# thermostat1.net
KiCad netlist of a schematic drawn in EAGLE
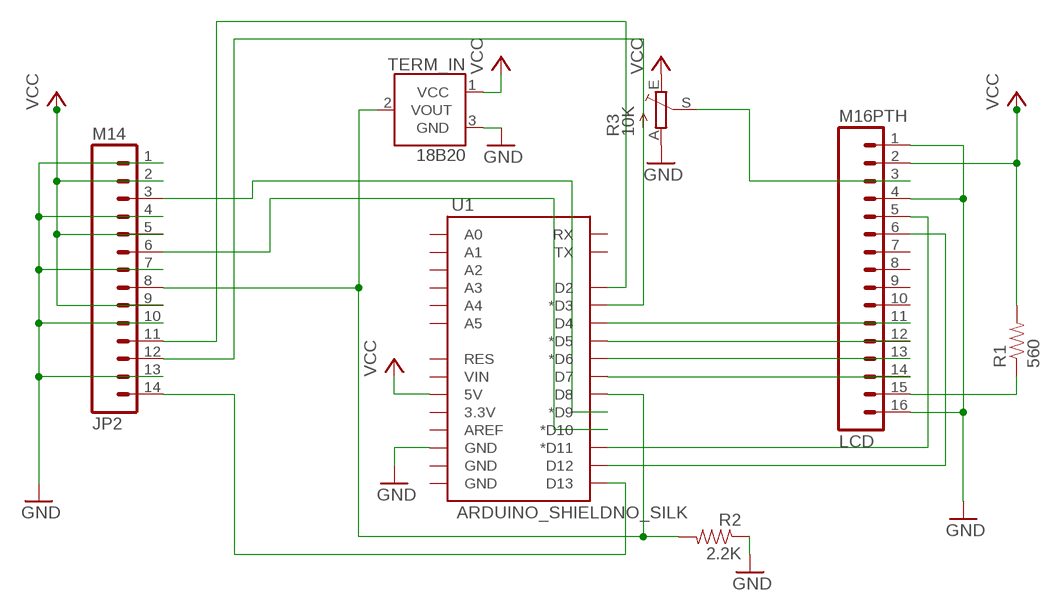
[diagram p0: schematic, sheet 1]

(export (version "E")
  (design (tool "Eeschema 10.0.6"))
  (components
    (comp (ref "JP2")
      (value "M14")
      (footprint "eagle-import:1X14")
      (libsource (lib "eagle-import") (part "M14"))
    )
    (comp (ref "LCD")
      (value "M16PTH")
      (footprint "eagle-import:1X16")
      (libsource (lib "eagle-import") (part "M16PTH"))
    )
    (comp (ref "R1")
      (value "560")
      (footprint "eagle-import:AXIAL-0.5")
      (libsource (lib "eagle-import") (part "RESISTORPTH-1/2W"))
    )
    (comp (ref "R2")
      (value "2.2K")
      (footprint "eagle-import:AXIAL-0.5")
      (libsource (lib "eagle-import") (part "RESISTORPTH-1/2W"))
    )
    (comp (ref "R3")
      (value "10K")
      (footprint "eagle-import:CA6V")
      (libsource (lib "eagle-import") (part "TRIM_EU-CA6V"))
    )
    (comp (ref "TERM_IN")
      (value "18B20")
      (footprint "eagle-import:TO-92")
      (libsource (lib "eagle-import") (part "TMP36GT9"))
    )
    (comp (ref "U1")
      (value "ARDUINO_SHIELDNO_SILK")
      (footprint "eagle-import:DUEMILANOVE_VIAS")
      (libsource (lib "eagle-import") (part "ARDUINO_SHIELDNO_SILK"))
    )
  )
  (nets
    (net (code "1") (name "GND") (class "Default")
      (node (ref "JP2") (pin "1") (pinfunction "1_1") (pintype "passive"))
      (node (ref "JP2") (pin "10") (pinfunction "10_10") (pintype "passive"))
      (node (ref "JP2") (pin "13") (pinfunction "13_13") (pintype "passive"))
      (node (ref "JP2") (pin "4") (pinfunction "4_4") (pintype "passive"))
      (node (ref "JP2") (pin "7") (pinfunction "7_7") (pintype "passive"))
      (node (ref "LCD") (pin "1") (pinfunction "1_1") (pintype "passive"))
      (node (ref "LCD") (pin "16") (pinfunction "16_16") (pintype "passive"))
      (node (ref "LCD") (pin "4") (pinfunction "4_4") (pintype "passive"))
      (node (ref "R2") (pin "P$1") (pinfunction "1_P$1") (pintype "passive"))
      (node (ref "R3") (pin "A") (pinfunction "A_A") (pintype "passive"))
      (node (ref "TERM_IN") (pin "3") (pinfunction "GND_3") (pintype "bidirectional"))
      (node (ref "U1") (pin "GND@2") (pinfunction "GND_GND@2") (pintype "bidirectional"))
    )
    (net (code "2") (name "Net-(JP2-Pad11)") (class "Default")
      (node (ref "JP2") (pin "11") (pinfunction "11_11") (pintype "passive"))
      (node (ref "U1") (pin "D2") (pinfunction "D2_D2") (pintype "bidirectional"))
    )
    (net (code "3") (name "Net-(JP2-Pad14)") (class "Default")
      (node (ref "JP2") (pin "14") (pinfunction "14_14") (pintype "passive"))
      (node (ref "U1") (pin "D13") (pinfunction "D13_D13") (pintype "bidirectional"))
    )
    (net (code "4") (name "Net-(LCD-Pad3)") (class "Default")
      (node (ref "LCD") (pin "3") (pinfunction "3_3") (pintype "passive"))
      (node (ref "R3") (pin "S") (pinfunction "S_S") (pintype "passive"))
    )
    (net (code "5") (name "Net-(LCD-Pad6)") (class "Default")
      (node (ref "LCD") (pin "6") (pinfunction "6_6") (pintype "passive"))
      (node (ref "U1") (pin "D12") (pinfunction "D12_D12") (pintype "bidirectional"))
    )
    (net (code "6") (name "Net-(LCD-Pad11)") (class "Default")
      (node (ref "LCD") (pin "11") (pinfunction "11_11") (pintype "passive"))
      (node (ref "U1") (pin "D4") (pinfunction "D4_D4") (pintype "bidirectional"))
    )
    (net (code "7") (name "Net-(LCD-Pad14)") (class "Default")
      (node (ref "LCD") (pin "14") (pinfunction "14_14") (pintype "passive"))
      (node (ref "U1") (pin "D7") (pinfunction "D7_D7") (pintype "bidirectional"))
    )
    (net (code "8") (name "Net-(R1-1)") (class "Default")
      (node (ref "LCD") (pin "15") (pinfunction "15_15") (pintype "passive"))
      (node (ref "R1") (pin "P$1") (pinfunction "1_P$1") (pintype "passive"))
    )
    (net (code "9") (name "Net-(R2-2)") (class "Default")
      (node (ref "JP2") (pin "8") (pinfunction "8_8") (pintype "passive"))
      (node (ref "R2") (pin "P$2") (pinfunction "2_P$2") (pintype "passive"))
      (node (ref "TERM_IN") (pin "2") (pinfunction "VOUT_2") (pintype "bidirectional"))
      (node (ref "U1") (pin "D8") (pinfunction "D8_D8") (pintype "bidirectional"))
    )
    (net (code "10") (name "Net-(U1-*D3)") (class "Default")
      (node (ref "JP2") (pin "12") (pinfunction "12_12") (pintype "passive"))
      (node (ref "U1") (pin "D3") (pinfunction "*D3_D3") (pintype "bidirectional"))
    )
    (net (code "11") (name "Net-(U1-*D5)") (class "Default")
      (node (ref "LCD") (pin "12") (pinfunction "12_12") (pintype "passive"))
      (node (ref "U1") (pin "D5") (pinfunction "*D5_D5") (pintype "bidirectional"))
    )
    (net (code "12") (name "Net-(U1-*D6)") (class "Default")
      (node (ref "LCD") (pin "13") (pinfunction "13_13") (pintype "passive"))
      (node (ref "U1") (pin "D6") (pinfunction "*D6_D6") (pintype "bidirectional"))
    )
    (net (code "13") (name "Net-(U1-*D9)") (class "Default")
      (node (ref "JP2") (pin "3") (pinfunction "3_3") (pintype "passive"))
      (node (ref "U1") (pin "D9") (pinfunction "*D9_D9") (pintype "bidirectional"))
    )
    (net (code "14") (name "Net-(U1-*D10)") (class "Default")
      (node (ref "JP2") (pin "6") (pinfunction "6_6") (pintype "passive"))
      (node (ref "U1") (pin "D10") (pinfunction "*D10_D10") (pintype "bidirectional"))
    )
    (net (code "15") (name "Net-(U1-*D11)") (class "Default")
      (node (ref "LCD") (pin "5") (pinfunction "5_5") (pintype "passive"))
      (node (ref "U1") (pin "D11") (pinfunction "*D11_D11") (pintype "bidirectional"))
    )
    (net (code "16") (name "VCC") (class "Default")
      (node (ref "JP2") (pin "2") (pinfunction "2_2") (pintype "passive"))
      (node (ref "JP2") (pin "5") (pinfunction "5_5") (pintype "passive"))
      (node (ref "JP2") (pin "9") (pinfunction "9_9") (pintype "passive"))
      (node (ref "LCD") (pin "2") (pinfunction "2_2") (pintype "passive"))
      (node (ref "R1") (pin "P$2") (pinfunction "2_P$2") (pintype "passive"))
      (node (ref "R3") (pin "E") (pinfunction "E_E") (pintype "passive"))
      (node (ref "TERM_IN") (pin "1") (pinfunction "VCC_1") (pintype "bidirectional"))
      (node (ref "U1") (pin "5V") (pinfunction "5V_5V") (pintype "bidirectional"))
    )
    (net (code "17") (name "unconnected-(LCD-Pad7)") (class "Default")
      (node (ref "LCD") (pin "7") (pinfunction "7_7") (pintype "passive"))
    )
    (net (code "18") (name "unconnected-(LCD-Pad8)") (class "Default")
      (node (ref "LCD") (pin "8") (pinfunction "8_8") (pintype "passive"))
    )
    (net (code "19") (name "unconnected-(LCD-Pad9)") (class "Default")
      (node (ref "LCD") (pin "9") (pinfunction "9_9") (pintype "passive"))
    )
    (net (code "20") (name "unconnected-(LCD-Pad10)") (class "Default")
      (node (ref "LCD") (pin "10") (pinfunction "10_10") (pintype "passive"))
    )
    (net (code "21") (name "unconnected-(U1-GND-PadGND@0)") (class "Default")
      (node (ref "U1") (pin "GND@0") (pinfunction "GND_GND@0") (pintype "bidirectional"))
    )
    (net (code "22") (name "unconnected-(U1-GND-PadGND@1)") (class "Default")
      (node (ref "U1") (pin "GND@1") (pinfunction "GND_GND@1") (pintype "bidirectional"))
    )
    (net (code "23") (name "unconnected-(U1-Pad3.3V)") (class "Default")
      (node (ref "U1") (pin "3.3V") (pinfunction "3.3V_3.3V") (pintype "bidirectional"))
    )
    (net (code "24") (name "unconnected-(U1-PadA0)") (class "Default")
      (node (ref "U1") (pin "A0") (pinfunction "A0_A0") (pintype "bidirectional"))
    )
    (net (code "25") (name "unconnected-(U1-PadA1)") (class "Default")
      (node (ref "U1") (pin "A1") (pinfunction "A1_A1") (pintype "bidirectional"))
    )
    (net (code "26") (name "unconnected-(U1-PadA2)") (class "Default")
      (node (ref "U1") (pin "A2") (pinfunction "A2_A2") (pintype "bidirectional"))
    )
    (net (code "27") (name "unconnected-(U1-PadA3)") (class "Default")
      (node (ref "U1") (pin "A3") (pinfunction "A3_A3") (pintype "bidirectional"))
    )
    (net (code "28") (name "unconnected-(U1-PadA4)") (class "Default")
      (node (ref "U1") (pin "A4") (pinfunction "A4_A4") (pintype "bidirectional"))
    )
    (net (code "29") (name "unconnected-(U1-PadA5)") (class "Default")
      (node (ref "U1") (pin "A5") (pinfunction "A5_A5") (pintype "bidirectional"))
    )
    (net (code "30") (name "unconnected-(U1-PadAREF)") (class "Default")
      (node (ref "U1") (pin "AREF") (pinfunction "AREF_AREF") (pintype "bidirectional"))
    )
    (net (code "31") (name "unconnected-(U1-PadRES)") (class "Default")
      (node (ref "U1") (pin "RES") (pinfunction "RES_RES") (pintype "bidirectional"))
    )
    (net (code "32") (name "unconnected-(U1-PadRX)") (class "Default")
      (node (ref "U1") (pin "RX") (pinfunction "RX_RX") (pintype "bidirectional"))
    )
    (net (code "33") (name "unconnected-(U1-PadTX)") (class "Default")
      (node (ref "U1") (pin "TX") (pinfunction "TX_TX") (pintype "bidirectional"))
    )
    (net (code "34") (name "unconnected-(U1-PadVIN)") (class "Default")
      (node (ref "U1") (pin "VIN") (pinfunction "VIN_VIN") (pintype "bidirectional"))
    )
  )
)
